# ECAL-TEST-MICRO-D.net
KiCad netlist of a schematic drawn in Altium Designer
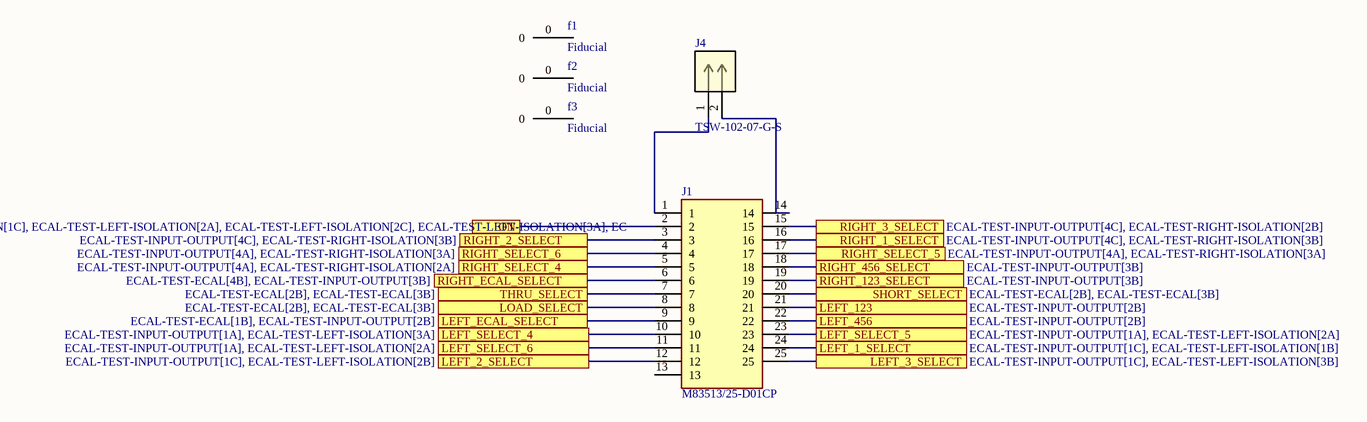
[diagram p0: ECAL-TEST-MICRO-D.SchDoc]

(export (version "E")
  (design (tool "Eeschema 10.0.6"))
  (components
    (comp (ref "f1") (value "Fiducial") (footprint "fiducial") (libsource (lib "Fiducial") (part "Fiducial")))
    (comp (ref "f2") (value "Fiducial") (footprint "fiducial") (libsource (lib "Fiducial") (part "Fiducial")))
    (comp (ref "f3") (value "Fiducial") (footprint "fiducial") (libsource (lib "Fiducial") (part "Fiducial")))
    (comp (ref "J1")
      (value "M83513/25-D01CP")
      (footprint "BEL_M83513/25-D01CP")
      (libsource (lib "SchlibLafe") (part "M83513/25-D01CP"))
    )
    (comp (ref "J4")
      (value "TSW-102-07-G-S")
      (footprint "CON2_1X2_TU_TSW")
      (description "No Description Available")
      (fields (field (name "COPYRIGHT") "Copyright (C) 2024 Ultra Librarian. All rights reserved."))
      (libsource (lib "SchlibLafe") (part "TSW-102-07-G-S"))
    )
  )
  (nets
    (net (code "1") (name "/LEFT_1_SELECT") (class "Default")
      (node (ref "J1") (pin "24") (pinfunction "24_24") (pintype "passive"))
    )
    (net (code "2") (name "/LEFT_2_SELECT") (class "Default")
      (node (ref "J1") (pin "12") (pinfunction "12_12") (pintype "passive"))
    )
    (net (code "3") (name "/LEFT_3_SELECT") (class "Default")
      (node (ref "J1") (pin "25") (pinfunction "25_25") (pintype "passive"))
    )
    (net (code "4") (name "/LEFT_123") (class "Default")
      (node (ref "J1") (pin "21") (pinfunction "21_21") (pintype "passive"))
    )
    (net (code "5") (name "/LEFT_456") (class "Default")
      (node (ref "J1") (pin "22") (pinfunction "22_22") (pintype "passive"))
    )
    (net (code "6") (name "/LEFT_ECAL_SELECT") (class "Default")
      (node (ref "J1") (pin "9") (pinfunction "9_9") (pintype "passive"))
    )
    (net (code "7") (name "/LEFT_SELECT_4") (class "Default")
      (node (ref "J1") (pin "10") (pinfunction "10_10") (pintype "passive"))
    )
    (net (code "8") (name "/LEFT_SELECT_5") (class "Default")
      (node (ref "J1") (pin "23") (pinfunction "23_23") (pintype "passive"))
    )
    (net (code "9") (name "/LEFT_SELECT_6") (class "Default")
      (node (ref "J1") (pin "11") (pinfunction "11_11") (pintype "passive"))
    )
    (net (code "10") (name "/LOAD_SELECT") (class "Default")
      (node (ref "J1") (pin "8") (pinfunction "8_8") (pintype "passive"))
    )
    (net (code "11") (name "/ON") (class "Default")
      (node (ref "J1") (pin "2") (pinfunction "2_2") (pintype "passive"))
    )
    (net (code "12") (name "/RIGHT_1_SELECT") (class "Default")
      (node (ref "J1") (pin "16") (pinfunction "16_16") (pintype "passive"))
    )
    (net (code "13") (name "/RIGHT_2_SELECT") (class "Default")
      (node (ref "J1") (pin "3") (pinfunction "3_3") (pintype "passive"))
    )
    (net (code "14") (name "/RIGHT_3_SELECT") (class "Default")
      (node (ref "J1") (pin "15") (pinfunction "15_15") (pintype "passive"))
    )
    (net (code "15") (name "/RIGHT_123_SELECT") (class "Default")
      (node (ref "J1") (pin "19") (pinfunction "19_19") (pintype "passive"))
    )
    (net (code "16") (name "/RIGHT_456_SELECT") (class "Default")
      (node (ref "J1") (pin "18") (pinfunction "18_18") (pintype "passive"))
    )
    (net (code "17") (name "/RIGHT_ECAL_SELECT") (class "Default")
      (node (ref "J1") (pin "6") (pinfunction "6_6") (pintype "passive"))
    )
    (net (code "18") (name "/RIGHT_SELECT_4") (class "Default")
      (node (ref "J1") (pin "5") (pinfunction "5_5") (pintype "passive"))
    )
    (net (code "19") (name "/RIGHT_SELECT_5") (class "Default")
      (node (ref "J1") (pin "17") (pinfunction "17_17") (pintype "passive"))
    )
    (net (code "20") (name "/RIGHT_SELECT_6") (class "Default")
      (node (ref "J1") (pin "4") (pinfunction "4_4") (pintype "passive"))
    )
    (net (code "21") (name "/SHORT_SELECT") (class "Default")
      (node (ref "J1") (pin "20") (pinfunction "20_20") (pintype "passive"))
    )
    (net (code "22") (name "/THRU_SELECT") (class "Default")
      (node (ref "J1") (pin "7") (pinfunction "7_7") (pintype "passive"))
    )
    (net (code "23") (name "Net-(J1-Pad1)") (class "Default")
      (node (ref "J1") (pin "1") (pinfunction "1_1") (pintype "passive"))
      (node (ref "J4") (pin "1") (pinfunction "1_1") (pintype "passive"))
    )
    (net (code "24") (name "Net-(J1-Pad14)") (class "Default")
      (node (ref "J1") (pin "14") (pinfunction "14_14") (pintype "passive"))
      (node (ref "J4") (pin "2") (pinfunction "2_2") (pintype "passive"))
    )
    (net (code "25") (name "unconnected-(J1-Pad13)") (class "Default")
      (node (ref "J1") (pin "13") (pinfunction "13_13") (pintype "passive"))
    )
    (net (code "26") (name "unconnected-(f1-Pad0)") (class "Default")
      (node (ref "f1") (pin "0") (pinfunction "0_0") (pintype "passive"))
    )
    (net (code "27") (name "unconnected-(f2-Pad0)") (class "Default")
      (node (ref "f2") (pin "0") (pinfunction "0_0") (pintype "passive"))
    )
    (net (code "28") (name "unconnected-(f3-Pad0)") (class "Default")
      (node (ref "f3") (pin "0") (pinfunction "0_0") (pintype "passive"))
    )
  )
)
